# camera.net
KiCad netlist of a schematic drawn in Altium Designer
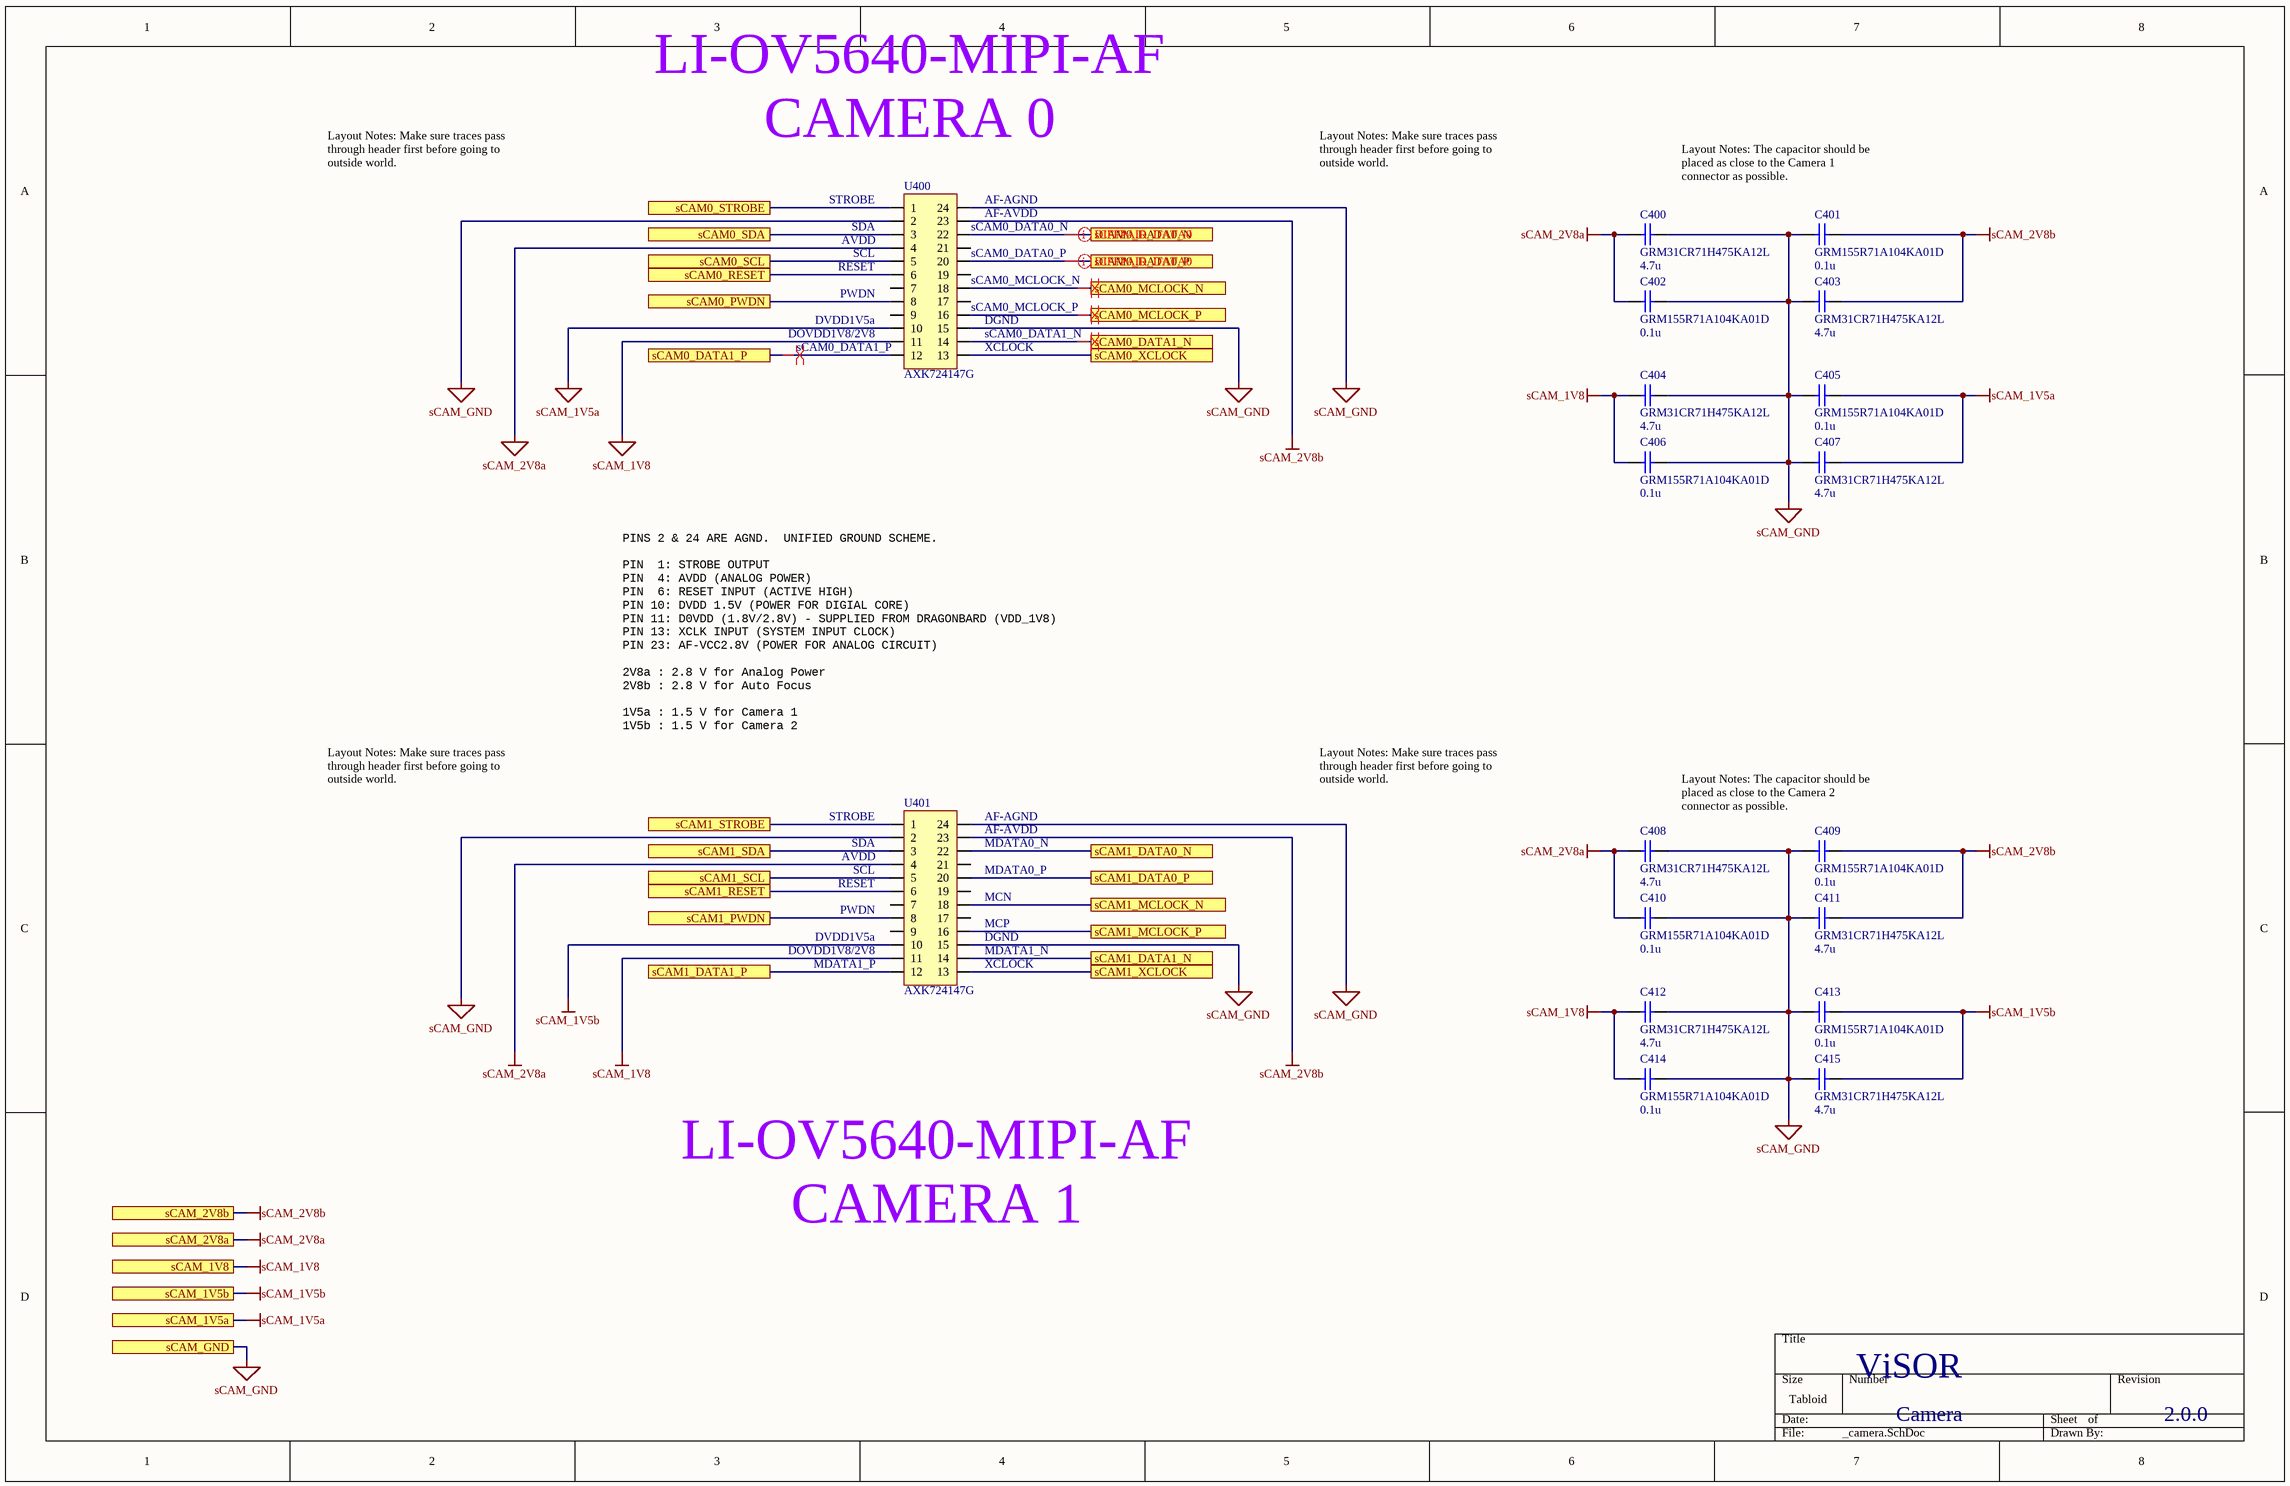
[diagram p0: _camera.SchDoc]

(export (version "E")
  (design (tool "Eeschema 10.0.6"))
  (components
    (comp (ref "C400")
      (value "GRM31CR71H475KA12L")
      (footprint "1206")
      (description "-55-125C, 3216, 50V, X7R, ±10%")
      (fields (field (name "ALTIUM_VALUE") "4.7u"))
      (libsource (lib "standard_capacitors") (part "GRM31CR71HxxxKdddd"))
    )
    (comp (ref "C401")
      (value "GRM155R71A104KA01D")
      (footprint "0402")
      (description "-55-125C, 1005, 10V, X7R, ±10%")
      (fields (field (name "ALTIUM_VALUE") "0.1u"))
      (libsource (lib "standard_capacitors") (part "GRM155R71AxxxKdddd"))
    )
    (comp (ref "C402")
      (value "GRM155R71A104KA01D")
      (footprint "0402")
      (description "-55-125C, 1005, 10V, X7R, ±10%")
      (fields (field (name "ALTIUM_VALUE") "0.1u"))
      (libsource (lib "standard_capacitors") (part "GRM155R71AxxxKdddd"))
    )
    (comp (ref "C403")
      (value "GRM31CR71H475KA12L")
      (footprint "1206")
      (description "-55-125C, 3216, 50V, X7R, ±10%")
      (fields (field (name "ALTIUM_VALUE") "4.7u"))
      (libsource (lib "standard_capacitors") (part "GRM31CR71HxxxKdddd"))
    )
    (comp (ref "C404")
      (value "GRM31CR71H475KA12L")
      (footprint "1206")
      (description "-55-125C, 3216, 50V, X7R, ±10%")
      (fields (field (name "ALTIUM_VALUE") "4.7u"))
      (libsource (lib "standard_capacitors") (part "GRM31CR71HxxxKdddd"))
    )
    (comp (ref "C405")
      (value "GRM155R71A104KA01D")
      (footprint "0402")
      (description "-55-125C, 1005, 10V, X7R, ±10%")
      (fields (field (name "ALTIUM_VALUE") "0.1u"))
      (libsource (lib "standard_capacitors") (part "GRM155R71AxxxKdddd"))
    )
    (comp (ref "C406")
      (value "GRM155R71A104KA01D")
      (footprint "0402")
      (description "-55-125C, 1005, 10V, X7R, ±10%")
      (fields (field (name "ALTIUM_VALUE") "0.1u"))
      (libsource (lib "standard_capacitors") (part "GRM155R71AxxxKdddd"))
    )
    (comp (ref "C407")
      (value "GRM31CR71H475KA12L")
      (footprint "1206")
      (description "-55-125C, 3216, 50V, X7R, ±10%")
      (fields (field (name "ALTIUM_VALUE") "4.7u"))
      (libsource (lib "standard_capacitors") (part "GRM31CR71HxxxKdddd"))
    )
    (comp (ref "C408")
      (value "GRM31CR71H475KA12L")
      (footprint "1206")
      (description "-55-125C, 3216, 50V, X7R, ±10%")
      (fields (field (name "ALTIUM_VALUE") "4.7u"))
      (libsource (lib "standard_capacitors") (part "GRM31CR71HxxxKdddd"))
    )
    (comp (ref "C409")
      (value "GRM155R71A104KA01D")
      (footprint "0402")
      (description "-55-125C, 1005, 10V, X7R, ±10%")
      (fields (field (name "ALTIUM_VALUE") "0.1u"))
      (libsource (lib "standard_capacitors") (part "GRM155R71AxxxKdddd"))
    )
    (comp (ref "C410")
      (value "GRM155R71A104KA01D")
      (footprint "0402")
      (description "-55-125C, 1005, 10V, X7R, ±10%")
      (fields (field (name "ALTIUM_VALUE") "0.1u"))
      (libsource (lib "standard_capacitors") (part "GRM155R71AxxxKdddd"))
    )
    (comp (ref "C411")
      (value "GRM31CR71H475KA12L")
      (footprint "1206")
      (description "-55-125C, 3216, 50V, X7R, ±10%")
      (fields (field (name "ALTIUM_VALUE") "4.7u"))
      (libsource (lib "standard_capacitors") (part "GRM31CR71HxxxKdddd"))
    )
    (comp (ref "C412")
      (value "GRM31CR71H475KA12L")
      (footprint "1206")
      (description "-55-125C, 3216, 50V, X7R, ±10%")
      (fields (field (name "ALTIUM_VALUE") "4.7u"))
      (libsource (lib "standard_capacitors") (part "GRM31CR71HxxxKdddd"))
    )
    (comp (ref "C413")
      (value "GRM155R71A104KA01D")
      (footprint "0402")
      (description "-55-125C, 1005, 10V, X7R, ±10%")
      (fields (field (name "ALTIUM_VALUE") "0.1u"))
      (libsource (lib "standard_capacitors") (part "GRM155R71AxxxKdddd"))
    )
    (comp (ref "C414")
      (value "GRM155R71A104KA01D")
      (footprint "0402")
      (description "-55-125C, 1005, 10V, X7R, ±10%")
      (fields (field (name "ALTIUM_VALUE") "0.1u"))
      (libsource (lib "standard_capacitors") (part "GRM155R71AxxxKdddd"))
    )
    (comp (ref "C415")
      (value "GRM31CR71H475KA12L")
      (footprint "1206")
      (description "-55-125C, 3216, 50V, X7R, ±10%")
      (fields (field (name "ALTIUM_VALUE") "4.7u"))
      (libsource (lib "standard_capacitors") (part "GRM31CR71HxxxKdddd"))
    )
    (comp (ref "U400")
      (value "AXK724147G")
      (footprint "AXK724147G")
      (description "CONN SOCKET P4 .4MM 24POS SMD")
      (libsource (lib "panasonic") (part "AXK724147G"))
    )
    (comp (ref "U401")
      (value "AXK724147G")
      (footprint "AXK724147G")
      (description "CONN SOCKET P4 .4MM 24POS SMD")
      (libsource (lib "panasonic") (part "AXK724147G"))
    )
  )
  (nets
    (net (code "1") (name "/sCAM0_DATA0_N") (class "Default")
      (node (ref "U400") (pin "22") (pinfunction "22_22") (pintype "passive"))
    )
    (net (code "2") (name "/sCAM0_DATA0_P") (class "Default")
      (node (ref "U400") (pin "20") (pinfunction "20_20") (pintype "passive"))
    )
    (net (code "3") (name "/sCAM0_DATA1_N") (class "Default")
      (node (ref "U400") (pin "14") (pinfunction "14_14") (pintype "passive"))
    )
    (net (code "4") (name "/sCAM0_DATA1_P") (class "Default")
      (node (ref "U400") (pin "12") (pinfunction "12_12") (pintype "passive"))
    )
    (net (code "5") (name "/sCAM0_MCLOCK_N") (class "Default")
      (node (ref "U400") (pin "18") (pinfunction "18_18") (pintype "passive"))
    )
    (net (code "6") (name "/sCAM0_MCLOCK_P") (class "Default")
      (node (ref "U400") (pin "16") (pinfunction "16_16") (pintype "passive"))
    )
    (net (code "7") (name "/sCAM0_PWDN") (class "Default")
      (node (ref "U400") (pin "8") (pinfunction "8_8") (pintype "passive"))
    )
    (net (code "8") (name "/sCAM0_RESET") (class "Default")
      (node (ref "U400") (pin "6") (pinfunction "6_6") (pintype "passive"))
    )
    (net (code "9") (name "/sCAM0_SCL") (class "Default")
      (node (ref "U400") (pin "5") (pinfunction "5_5") (pintype "passive"))
    )
    (net (code "10") (name "/sCAM0_SDA") (class "Default")
      (node (ref "U400") (pin "3") (pinfunction "3_3") (pintype "passive"))
    )
    (net (code "11") (name "/sCAM0_STROBE") (class "Default")
      (node (ref "U400") (pin "1") (pinfunction "1_1") (pintype "passive"))
    )
    (net (code "12") (name "/sCAM0_XCLOCK") (class "Default")
      (node (ref "U400") (pin "13") (pinfunction "13_13") (pintype "passive"))
    )
    (net (code "13") (name "/sCAM1_DATA0_N") (class "Default")
      (node (ref "U401") (pin "22") (pinfunction "22_22") (pintype "passive"))
    )
    (net (code "14") (name "/sCAM1_DATA0_P") (class "Default")
      (node (ref "U401") (pin "20") (pinfunction "20_20") (pintype "passive"))
    )
    (net (code "15") (name "/sCAM1_DATA1_N") (class "Default")
      (node (ref "U401") (pin "14") (pinfunction "14_14") (pintype "passive"))
    )
    (net (code "16") (name "/sCAM1_DATA1_P") (class "Default")
      (node (ref "U401") (pin "12") (pinfunction "12_12") (pintype "passive"))
    )
    (net (code "17") (name "/sCAM1_MCLOCK_N") (class "Default")
      (node (ref "U401") (pin "18") (pinfunction "18_18") (pintype "passive"))
    )
    (net (code "18") (name "/sCAM1_MCLOCK_P") (class "Default")
      (node (ref "U401") (pin "16") (pinfunction "16_16") (pintype "passive"))
    )
    (net (code "19") (name "/sCAM1_PWDN") (class "Default")
      (node (ref "U401") (pin "8") (pinfunction "8_8") (pintype "passive"))
    )
    (net (code "20") (name "/sCAM1_RESET") (class "Default")
      (node (ref "U401") (pin "6") (pinfunction "6_6") (pintype "passive"))
    )
    (net (code "21") (name "/sCAM1_SCL") (class "Default")
      (node (ref "U401") (pin "5") (pinfunction "5_5") (pintype "passive"))
    )
    (net (code "22") (name "/sCAM1_SDA") (class "Default")
      (node (ref "U401") (pin "3") (pinfunction "3_3") (pintype "passive"))
    )
    (net (code "23") (name "/sCAM1_STROBE") (class "Default")
      (node (ref "U401") (pin "1") (pinfunction "1_1") (pintype "passive"))
    )
    (net (code "24") (name "/sCAM1_XCLOCK") (class "Default")
      (node (ref "U401") (pin "13") (pinfunction "13_13") (pintype "passive"))
    )
    (net (code "25") (name "sCAM_1V5a") (class "Default")
      (node (ref "C405") (pin "2") (pinfunction "2_2") (pintype "passive"))
      (node (ref "C407") (pin "1") (pinfunction "1_1") (pintype "passive"))
      (node (ref "U400") (pin "10") (pinfunction "10_10") (pintype "passive"))
    )
    (net (code "26") (name "sCAM_1V5b") (class "Default")
      (node (ref "C413") (pin "2") (pinfunction "2_2") (pintype "passive"))
      (node (ref "C415") (pin "1") (pinfunction "1_1") (pintype "passive"))
      (node (ref "U401") (pin "10") (pinfunction "10_10") (pintype "passive"))
    )
    (net (code "27") (name "sCAM_1V8") (class "Default")
      (node (ref "C404") (pin "1") (pinfunction "1_1") (pintype "passive"))
      (node (ref "C406") (pin "2") (pinfunction "2_2") (pintype "passive"))
      (node (ref "C412") (pin "1") (pinfunction "1_1") (pintype "passive"))
      (node (ref "C414") (pin "2") (pinfunction "2_2") (pintype "passive"))
      (node (ref "U400") (pin "11") (pinfunction "11_11") (pintype "passive"))
      (node (ref "U401") (pin "11") (pinfunction "11_11") (pintype "passive"))
    )
    (net (code "28") (name "sCAM_2V8a") (class "Default")
      (node (ref "C400") (pin "1") (pinfunction "1_1") (pintype "passive"))
      (node (ref "C402") (pin "2") (pinfunction "2_2") (pintype "passive"))
      (node (ref "C408") (pin "1") (pinfunction "1_1") (pintype "passive"))
      (node (ref "C410") (pin "2") (pinfunction "2_2") (pintype "passive"))
      (node (ref "U400") (pin "4") (pinfunction "4_4") (pintype "passive"))
      (node (ref "U401") (pin "4") (pinfunction "4_4") (pintype "passive"))
    )
    (net (code "29") (name "sCAM_2V8b") (class "Default")
      (node (ref "C401") (pin "2") (pinfunction "2_2") (pintype "passive"))
      (node (ref "C403") (pin "1") (pinfunction "1_1") (pintype "passive"))
      (node (ref "C409") (pin "2") (pinfunction "2_2") (pintype "passive"))
      (node (ref "C411") (pin "1") (pinfunction "1_1") (pintype "passive"))
      (node (ref "U400") (pin "23") (pinfunction "23_23") (pintype "passive"))
      (node (ref "U401") (pin "23") (pinfunction "23_23") (pintype "passive"))
    )
    (net (code "30") (name "sCAM_GND") (class "Default")
      (node (ref "C400") (pin "2") (pinfunction "2_2") (pintype "passive"))
      (node (ref "C401") (pin "1") (pinfunction "1_1") (pintype "passive"))
      (node (ref "C402") (pin "1") (pinfunction "1_1") (pintype "passive"))
      (node (ref "C403") (pin "2") (pinfunction "2_2") (pintype "passive"))
      (node (ref "C404") (pin "2") (pinfunction "2_2") (pintype "passive"))
      (node (ref "C405") (pin "1") (pinfunction "1_1") (pintype "passive"))
      (node (ref "C406") (pin "1") (pinfunction "1_1") (pintype "passive"))
      (node (ref "C407") (pin "2") (pinfunction "2_2") (pintype "passive"))
      (node (ref "C408") (pin "2") (pinfunction "2_2") (pintype "passive"))
      (node (ref "C409") (pin "1") (pinfunction "1_1") (pintype "passive"))
      (node (ref "C410") (pin "1") (pinfunction "1_1") (pintype "passive"))
      (node (ref "C411") (pin "2") (pinfunction "2_2") (pintype "passive"))
      (node (ref "C412") (pin "2") (pinfunction "2_2") (pintype "passive"))
      (node (ref "C413") (pin "1") (pinfunction "1_1") (pintype "passive"))
      (node (ref "C414") (pin "1") (pinfunction "1_1") (pintype "passive"))
      (node (ref "C415") (pin "2") (pinfunction "2_2") (pintype "passive"))
      (node (ref "U400") (pin "15") (pinfunction "15_15") (pintype "passive"))
      (node (ref "U400") (pin "2") (pinfunction "2_2") (pintype "passive"))
      (node (ref "U400") (pin "24") (pinfunction "24_24") (pintype "passive"))
      (node (ref "U401") (pin "15") (pinfunction "15_15") (pintype "passive"))
      (node (ref "U401") (pin "2") (pinfunction "2_2") (pintype "passive"))
      (node (ref "U401") (pin "24") (pinfunction "24_24") (pintype "passive"))
    )
    (net (code "31") (name "unconnected-(U400-Pad7)") (class "Default")
      (node (ref "U400") (pin "7") (pinfunction "7_7") (pintype "passive"))
    )
    (net (code "32") (name "unconnected-(U400-Pad9)") (class "Default")
      (node (ref "U400") (pin "9") (pinfunction "9_9") (pintype "passive"))
    )
    (net (code "33") (name "unconnected-(U400-Pad17)") (class "Default")
      (node (ref "U400") (pin "17") (pinfunction "17_17") (pintype "passive"))
    )
    (net (code "34") (name "unconnected-(U400-Pad19)") (class "Default")
      (node (ref "U400") (pin "19") (pinfunction "19_19") (pintype "passive"))
    )
    (net (code "35") (name "unconnected-(U400-Pad21)") (class "Default")
      (node (ref "U400") (pin "21") (pinfunction "21_21") (pintype "passive"))
    )
    (net (code "36") (name "unconnected-(U401-Pad7)") (class "Default")
      (node (ref "U401") (pin "7") (pinfunction "7_7") (pintype "passive"))
    )
    (net (code "37") (name "unconnected-(U401-Pad9)") (class "Default")
      (node (ref "U401") (pin "9") (pinfunction "9_9") (pintype "passive"))
    )
    (net (code "38") (name "unconnected-(U401-Pad17)") (class "Default")
      (node (ref "U401") (pin "17") (pinfunction "17_17") (pintype "passive"))
    )
    (net (code "39") (name "unconnected-(U401-Pad19)") (class "Default")
      (node (ref "U401") (pin "19") (pinfunction "19_19") (pintype "passive"))
    )
    (net (code "40") (name "unconnected-(U401-Pad21)") (class "Default")
      (node (ref "U401") (pin "21") (pinfunction "21_21") (pintype "passive"))
    )
  )
)
